# LeguinoNano.net
KiCad netlist of a schematic drawn in EAGLE
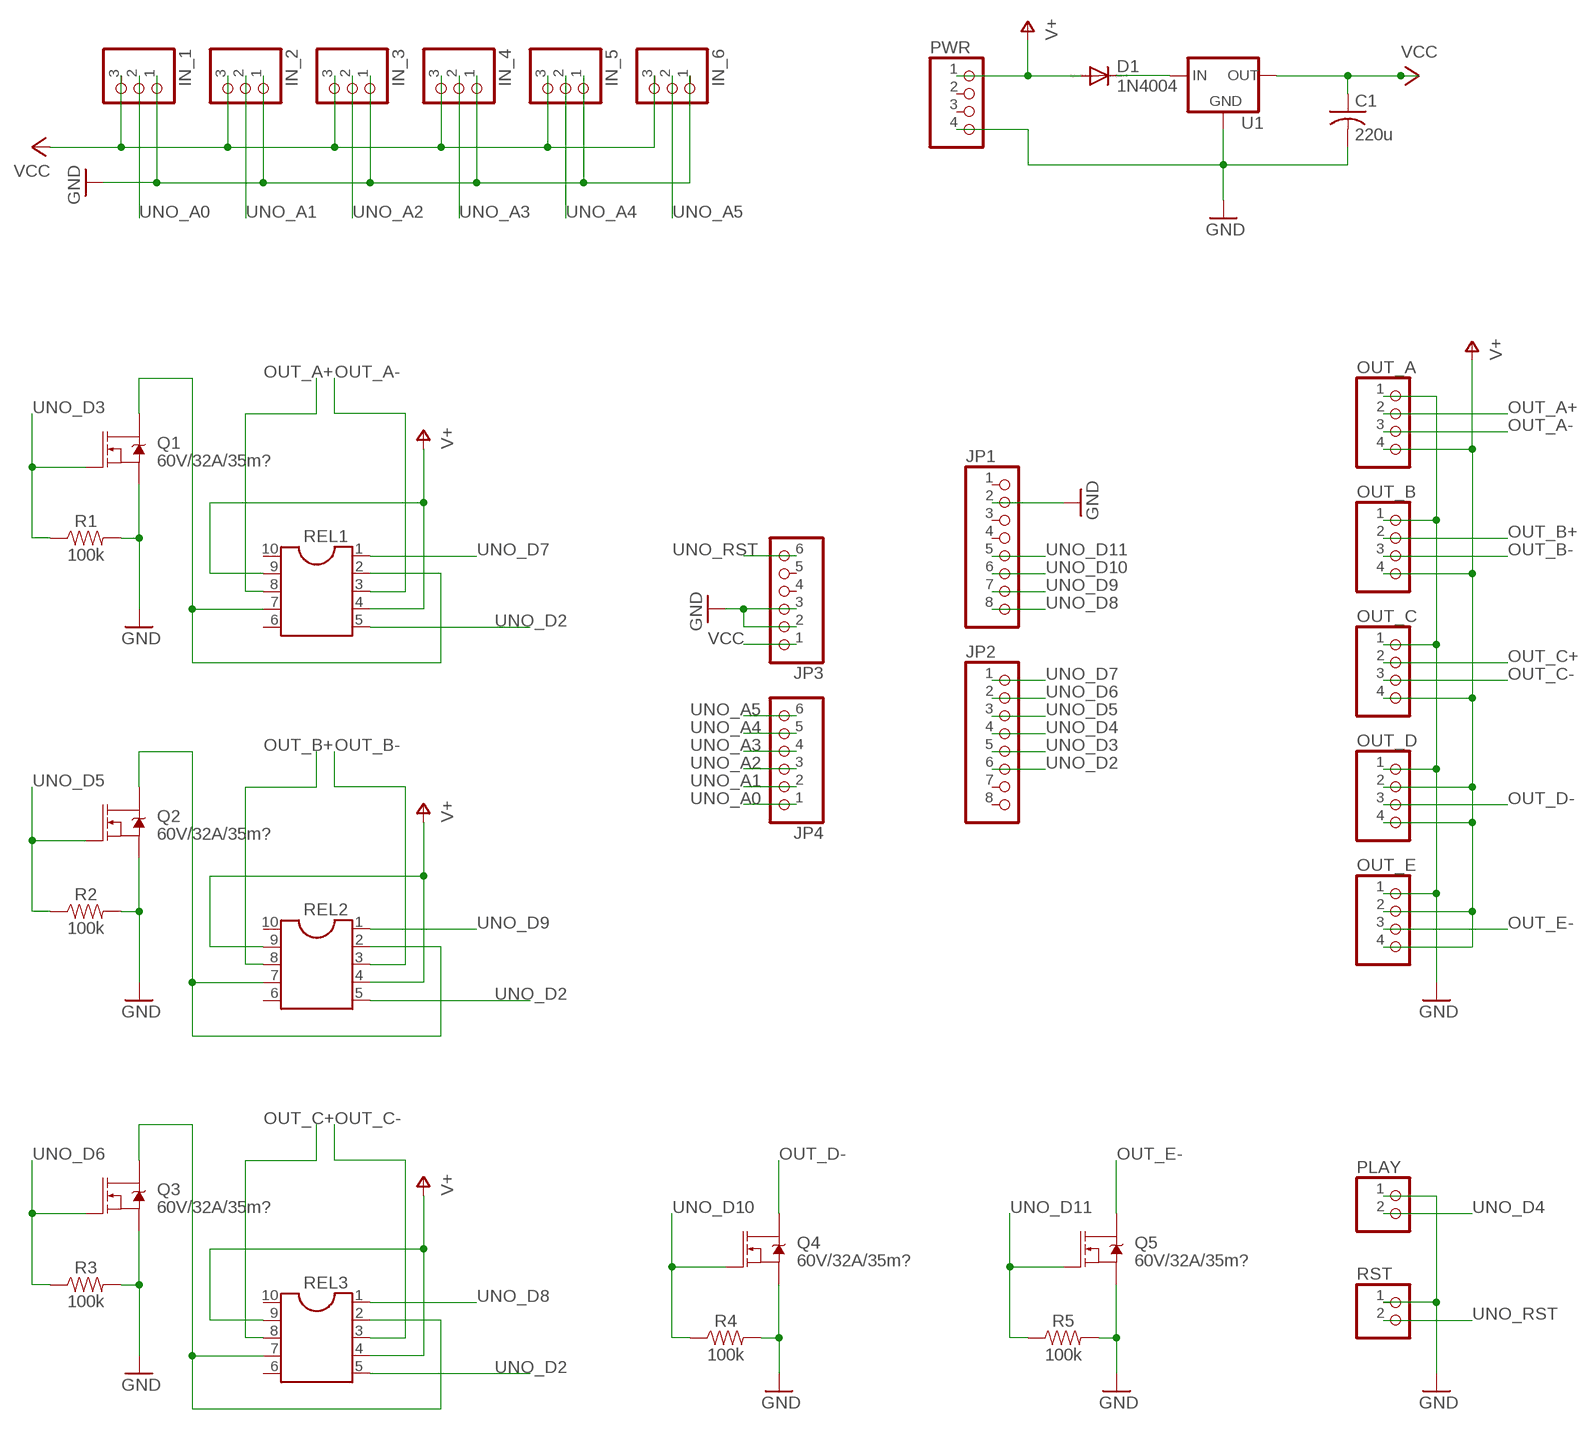
[diagram p0: schematic, sheet 1]

(export (version "E")
  (design (tool "Eeschema 10.0.6"))
  (components
    (comp (ref "C1")
      (value "220u")
      (footprint "eagle-import:C050-030X075")
      (libsource (lib "eagle-import") (part "C-US050-030X075"))
    )
    (comp (ref "D1")
      (value "1N4004")
      (footprint "eagle-import:DO41-10")
      (libsource (lib "eagle-import") (part "1N4004"))
    )
    (comp (ref "IN_1")
      (value "PINHD-1X3")
      (footprint "eagle-import:1X03")
      (libsource (lib "eagle-import") (part "PINHD-1X3"))
    )
    (comp (ref "IN_2")
      (value "PINHD-1X3")
      (footprint "eagle-import:1X03")
      (libsource (lib "eagle-import") (part "PINHD-1X3"))
    )
    (comp (ref "IN_3")
      (value "PINHD-1X3")
      (footprint "eagle-import:1X03")
      (libsource (lib "eagle-import") (part "PINHD-1X3"))
    )
    (comp (ref "IN_4")
      (value "PINHD-1X3")
      (footprint "eagle-import:1X03")
      (libsource (lib "eagle-import") (part "PINHD-1X3"))
    )
    (comp (ref "IN_5")
      (value "PINHD-1X3")
      (footprint "eagle-import:1X03")
      (libsource (lib "eagle-import") (part "PINHD-1X3"))
    )
    (comp (ref "IN_6")
      (value "PINHD-1X3")
      (footprint "eagle-import:1X03")
      (libsource (lib "eagle-import") (part "PINHD-1X3"))
    )
    (comp (ref "JP1")
      (value "PINHD-1X8")
      (footprint "eagle-import:1X08")
      (libsource (lib "eagle-import") (part "PINHD-1X8"))
    )
    (comp (ref "JP2")
      (value "PINHD-1X8")
      (footprint "eagle-import:1X08")
      (libsource (lib "eagle-import") (part "PINHD-1X8"))
    )
    (comp (ref "JP3")
      (value "PINHD-1X6")
      (footprint "eagle-import:1X06")
      (libsource (lib "eagle-import") (part "PINHD-1X6"))
    )
    (comp (ref "JP4")
      (value "PINHD-1X6")
      (footprint "eagle-import:1X06")
      (libsource (lib "eagle-import") (part "PINHD-1X6"))
    )
    (comp (ref "OUT_A")
      (value "PINHD-1X4")
      (footprint "eagle-import:1X04")
      (libsource (lib "eagle-import") (part "PINHD-1X4"))
    )
    (comp (ref "OUT_B")
      (value "PINHD-1X4")
      (footprint "eagle-import:1X04")
      (libsource (lib "eagle-import") (part "PINHD-1X4"))
    )
    (comp (ref "OUT_C")
      (value "PINHD-1X4")
      (footprint "eagle-import:1X04")
      (libsource (lib "eagle-import") (part "PINHD-1X4"))
    )
    (comp (ref "OUT_D")
      (value "PINHD-1X4")
      (footprint "eagle-import:1X04")
      (libsource (lib "eagle-import") (part "PINHD-1X4"))
    )
    (comp (ref "OUT_E")
      (value "PINHD-1X4")
      (footprint "eagle-import:1X04")
      (libsource (lib "eagle-import") (part "PINHD-1X4"))
    )
    (comp (ref "PLAY")
      (value "PINHD-1X2")
      (footprint "eagle-import:1X02")
      (libsource (lib "eagle-import") (part "PINHD-1X2"))
    )
    (comp (ref "PWR")
      (value "PINHD-1X4")
      (footprint "eagle-import:1X04")
      (libsource (lib "eagle-import") (part "PINHD-1X4"))
    )
    (comp (ref "Q1")
      (value "60V/32A/35m?")
      (footprint "eagle-import:TO220V")
      (libsource (lib "eagle-import") (part "MOSFET-NCH-FQP30N06L"))
    )
    (comp (ref "Q2")
      (value "60V/32A/35m?")
      (footprint "eagle-import:TO220V")
      (libsource (lib "eagle-import") (part "MOSFET-NCH-FQP30N06L"))
    )
    (comp (ref "Q3")
      (value "60V/32A/35m?")
      (footprint "eagle-import:TO220V")
      (libsource (lib "eagle-import") (part "MOSFET-NCH-FQP30N06L"))
    )
    (comp (ref "Q4")
      (value "60V/32A/35m?")
      (footprint "eagle-import:TO220V")
      (libsource (lib "eagle-import") (part "MOSFET-NCH-FQP30N06L"))
    )
    (comp (ref "Q5")
      (value "60V/32A/35m?")
      (footprint "eagle-import:TO220V")
      (libsource (lib "eagle-import") (part "MOSFET-NCH-FQP30N06L"))
    )
    (comp (ref "R1")
      (value "100k")
      (footprint "eagle-import:AXIAL-0.3")
      (libsource (lib "eagle-import") (part "100KOHM-HORIZ-1/4W-1%"))
    )
    (comp (ref "R2")
      (value "100k")
      (footprint "eagle-import:AXIAL-0.3")
      (libsource (lib "eagle-import") (part "100KOHM-HORIZ-1/4W-1%"))
    )
    (comp (ref "R3")
      (value "100k")
      (footprint "eagle-import:AXIAL-0.3")
      (libsource (lib "eagle-import") (part "100KOHM-HORIZ-1/4W-1%"))
    )
    (comp (ref "R4")
      (value "100k")
      (footprint "eagle-import:AXIAL-0.3")
      (libsource (lib "eagle-import") (part "100KOHM-HORIZ-1/4W-1%"))
    )
    (comp (ref "R5")
      (value "100k")
      (footprint "eagle-import:AXIAL-0.3")
      (libsource (lib "eagle-import") (part "100KOHM-HORIZ-1/4W-1%"))
    )
    (comp (ref "REL1")
      (value "DIL10")
      (footprint "eagle-import:DIL10")
      (libsource (lib "eagle-import") (part "DIL10"))
    )
    (comp (ref "REL2")
      (value "DIL10")
      (footprint "eagle-import:DIL10")
      (libsource (lib "eagle-import") (part "DIL10"))
    )
    (comp (ref "REL3")
      (value "DIL10")
      (footprint "eagle-import:DIL10")
      (libsource (lib "eagle-import") (part "DIL10"))
    )
    (comp (ref "RST")
      (value "PINHD-1X2")
      (footprint "eagle-import:1X02")
      (libsource (lib "eagle-import") (part "PINHD-1X2"))
    )
    (comp (ref "U1")
      (value "V_REG_78XX-TO-220")
      (footprint "eagle-import:TO-220-ALT")
      (libsource (lib "eagle-import") (part "V_REG_78XX-TO-220"))
    )
  )
  (nets
    (net (code "1") (name "/OUT_A+") (class "Default")
      (node (ref "OUT_A") (pin "2") (pinfunction "2_2") (pintype "passive"))
      (node (ref "REL1") (pin "8") (pinfunction "8_8") (pintype "passive"))
    )
    (net (code "2") (name "/OUT_A-") (class "Default")
      (node (ref "OUT_A") (pin "3") (pinfunction "3_3") (pintype "passive"))
      (node (ref "REL1") (pin "3") (pinfunction "3_3") (pintype "passive"))
    )
    (net (code "3") (name "/OUT_B+") (class "Default")
      (node (ref "OUT_B") (pin "2") (pinfunction "2_2") (pintype "passive"))
      (node (ref "REL2") (pin "8") (pinfunction "8_8") (pintype "passive"))
    )
    (net (code "4") (name "/OUT_B-") (class "Default")
      (node (ref "OUT_B") (pin "3") (pinfunction "3_3") (pintype "passive"))
      (node (ref "REL2") (pin "3") (pinfunction "3_3") (pintype "passive"))
    )
    (net (code "5") (name "/OUT_C+") (class "Default")
      (node (ref "OUT_C") (pin "2") (pinfunction "2_2") (pintype "passive"))
      (node (ref "REL3") (pin "8") (pinfunction "8_8") (pintype "passive"))
    )
    (net (code "6") (name "/OUT_C-") (class "Default")
      (node (ref "OUT_C") (pin "3") (pinfunction "3_3") (pintype "passive"))
      (node (ref "REL3") (pin "3") (pinfunction "3_3") (pintype "passive"))
    )
    (net (code "7") (name "/OUT_D-") (class "Default")
      (node (ref "OUT_D") (pin "3") (pinfunction "3_3") (pintype "passive"))
      (node (ref "Q4") (pin "2") (pinfunction "D_2") (pintype "bidirectional"))
    )
    (net (code "8") (name "/OUT_E-") (class "Default")
      (node (ref "OUT_E") (pin "3") (pinfunction "3_3") (pintype "passive"))
      (node (ref "Q5") (pin "2") (pinfunction "D_2") (pintype "bidirectional"))
    )
    (net (code "9") (name "/UNO_A0") (class "Default")
      (node (ref "IN_1") (pin "2") (pinfunction "2_2") (pintype "passive"))
      (node (ref "JP4") (pin "1") (pinfunction "1_1") (pintype "passive"))
    )
    (net (code "10") (name "/UNO_A1") (class "Default")
      (node (ref "IN_2") (pin "2") (pinfunction "2_2") (pintype "passive"))
      (node (ref "JP4") (pin "2") (pinfunction "2_2") (pintype "passive"))
    )
    (net (code "11") (name "/UNO_A2") (class "Default")
      (node (ref "IN_3") (pin "2") (pinfunction "2_2") (pintype "passive"))
      (node (ref "JP4") (pin "3") (pinfunction "3_3") (pintype "passive"))
    )
    (net (code "12") (name "/UNO_A3") (class "Default")
      (node (ref "IN_4") (pin "2") (pinfunction "2_2") (pintype "passive"))
      (node (ref "JP4") (pin "4") (pinfunction "4_4") (pintype "passive"))
    )
    (net (code "13") (name "/UNO_A4") (class "Default")
      (node (ref "IN_5") (pin "2") (pinfunction "2_2") (pintype "passive"))
      (node (ref "JP4") (pin "5") (pinfunction "5_5") (pintype "passive"))
    )
    (net (code "14") (name "/UNO_A5") (class "Default")
      (node (ref "IN_6") (pin "2") (pinfunction "2_2") (pintype "passive"))
      (node (ref "JP4") (pin "6") (pinfunction "6_6") (pintype "passive"))
    )
    (net (code "15") (name "/UNO_D2") (class "Default")
      (node (ref "JP2") (pin "6") (pinfunction "6_6") (pintype "passive"))
      (node (ref "REL1") (pin "5") (pinfunction "5_5") (pintype "passive"))
      (node (ref "REL2") (pin "5") (pinfunction "5_5") (pintype "passive"))
      (node (ref "REL3") (pin "5") (pinfunction "5_5") (pintype "passive"))
    )
    (net (code "16") (name "/UNO_D3") (class "Default")
      (node (ref "JP2") (pin "5") (pinfunction "5_5") (pintype "passive"))
      (node (ref "Q1") (pin "1") (pinfunction "G_1") (pintype "bidirectional"))
      (node (ref "R1") (pin "P$1") (pinfunction "1_P$1") (pintype "passive"))
    )
    (net (code "17") (name "/UNO_D4") (class "Default")
      (node (ref "JP2") (pin "4") (pinfunction "4_4") (pintype "passive"))
      (node (ref "PLAY") (pin "2") (pinfunction "2_2") (pintype "passive"))
    )
    (net (code "18") (name "/UNO_D5") (class "Default")
      (node (ref "JP2") (pin "3") (pinfunction "3_3") (pintype "passive"))
      (node (ref "Q2") (pin "1") (pinfunction "G_1") (pintype "bidirectional"))
      (node (ref "R2") (pin "P$1") (pinfunction "1_P$1") (pintype "passive"))
    )
    (net (code "19") (name "/UNO_D6") (class "Default")
      (node (ref "JP2") (pin "2") (pinfunction "2_2") (pintype "passive"))
      (node (ref "Q3") (pin "1") (pinfunction "G_1") (pintype "bidirectional"))
      (node (ref "R3") (pin "P$1") (pinfunction "1_P$1") (pintype "passive"))
    )
    (net (code "20") (name "/UNO_D7") (class "Default")
      (node (ref "JP2") (pin "1") (pinfunction "1_1") (pintype "passive"))
      (node (ref "REL1") (pin "1") (pinfunction "1_1") (pintype "passive"))
    )
    (net (code "21") (name "/UNO_D8") (class "Default")
      (node (ref "JP1") (pin "8") (pinfunction "8_8") (pintype "passive"))
      (node (ref "REL3") (pin "1") (pinfunction "1_1") (pintype "passive"))
    )
    (net (code "22") (name "/UNO_D9") (class "Default")
      (node (ref "JP1") (pin "7") (pinfunction "7_7") (pintype "passive"))
      (node (ref "REL2") (pin "1") (pinfunction "1_1") (pintype "passive"))
    )
    (net (code "23") (name "/UNO_D10") (class "Default")
      (node (ref "JP1") (pin "6") (pinfunction "6_6") (pintype "passive"))
      (node (ref "Q4") (pin "1") (pinfunction "G_1") (pintype "bidirectional"))
      (node (ref "R4") (pin "P$1") (pinfunction "1_P$1") (pintype "passive"))
    )
    (net (code "24") (name "/UNO_D11") (class "Default")
      (node (ref "JP1") (pin "5") (pinfunction "5_5") (pintype "passive"))
      (node (ref "Q5") (pin "1") (pinfunction "G_1") (pintype "bidirectional"))
      (node (ref "R5") (pin "P$1") (pinfunction "1_P$1") (pintype "passive"))
    )
    (net (code "25") (name "/UNO_RST") (class "Default")
      (node (ref "JP3") (pin "6") (pinfunction "6_6") (pintype "passive"))
      (node (ref "RST") (pin "2") (pinfunction "2_2") (pintype "passive"))
    )
    (net (code "26") (name "GND") (class "Default")
      (node (ref "C1") (pin "2") (pinfunction "2_2") (pintype "passive"))
      (node (ref "IN_1") (pin "1") (pinfunction "1_1") (pintype "passive"))
      (node (ref "IN_2") (pin "1") (pinfunction "1_1") (pintype "passive"))
      (node (ref "IN_3") (pin "1") (pinfunction "1_1") (pintype "passive"))
      (node (ref "IN_4") (pin "1") (pinfunction "1_1") (pintype "passive"))
      (node (ref "IN_5") (pin "1") (pinfunction "1_1") (pintype "passive"))
      (node (ref "IN_6") (pin "1") (pinfunction "1_1") (pintype "passive"))
      (node (ref "JP1") (pin "2") (pinfunction "2_2") (pintype "passive"))
      (node (ref "JP3") (pin "2") (pinfunction "2_2") (pintype "passive"))
      (node (ref "JP3") (pin "3") (pinfunction "3_3") (pintype "passive"))
      (node (ref "OUT_A") (pin "1") (pinfunction "1_1") (pintype "passive"))
      (node (ref "OUT_B") (pin "1") (pinfunction "1_1") (pintype "passive"))
      (node (ref "OUT_C") (pin "1") (pinfunction "1_1") (pintype "passive"))
      (node (ref "OUT_D") (pin "1") (pinfunction "1_1") (pintype "passive"))
      (node (ref "OUT_E") (pin "1") (pinfunction "1_1") (pintype "passive"))
      (node (ref "PLAY") (pin "1") (pinfunction "1_1") (pintype "passive"))
      (node (ref "PWR") (pin "4") (pinfunction "4_4") (pintype "passive"))
      (node (ref "Q1") (pin "3") (pinfunction "S_3") (pintype "bidirectional"))
      (node (ref "Q2") (pin "3") (pinfunction "S_3") (pintype "bidirectional"))
      (node (ref "Q3") (pin "3") (pinfunction "S_3") (pintype "bidirectional"))
      (node (ref "Q4") (pin "3") (pinfunction "S_3") (pintype "bidirectional"))
      (node (ref "Q5") (pin "3") (pinfunction "S_3") (pintype "bidirectional"))
      (node (ref "R1") (pin "P$2") (pinfunction "2_P$2") (pintype "passive"))
      (node (ref "R2") (pin "P$2") (pinfunction "2_P$2") (pintype "passive"))
      (node (ref "R3") (pin "P$2") (pinfunction "2_P$2") (pintype "passive"))
      (node (ref "R4") (pin "P$2") (pinfunction "2_P$2") (pintype "passive"))
      (node (ref "R5") (pin "P$2") (pinfunction "2_P$2") (pintype "passive"))
      (node (ref "RST") (pin "1") (pinfunction "1_1") (pintype "passive"))
      (node (ref "U1") (pin "GND") (pinfunction "GND_GND") (pintype "input"))
    )
    (net (code "27") (name "Net-(D1-PadC)") (class "Default")
      (node (ref "D1") (pin "C") (pinfunction "C_C") (pintype "passive"))
      (node (ref "U1") (pin "IN") (pinfunction "IN_IN") (pintype "input"))
    )
    (net (code "28") (name "Net-(Q1-D)") (class "Default")
      (node (ref "Q1") (pin "2") (pinfunction "D_2") (pintype "bidirectional"))
      (node (ref "REL1") (pin "2") (pinfunction "2_2") (pintype "passive"))
      (node (ref "REL1") (pin "7") (pinfunction "7_7") (pintype "passive"))
    )
    (net (code "29") (name "Net-(Q2-D)") (class "Default")
      (node (ref "Q2") (pin "2") (pinfunction "D_2") (pintype "bidirectional"))
      (node (ref "REL2") (pin "2") (pinfunction "2_2") (pintype "passive"))
      (node (ref "REL2") (pin "7") (pinfunction "7_7") (pintype "passive"))
    )
    (net (code "30") (name "Net-(Q3-D)") (class "Default")
      (node (ref "Q3") (pin "2") (pinfunction "D_2") (pintype "bidirectional"))
      (node (ref "REL3") (pin "2") (pinfunction "2_2") (pintype "passive"))
      (node (ref "REL3") (pin "7") (pinfunction "7_7") (pintype "passive"))
    )
    (net (code "31") (name "V+") (class "Default")
      (node (ref "D1") (pin "A") (pinfunction "A_A") (pintype "passive"))
      (node (ref "OUT_A") (pin "4") (pinfunction "4_4") (pintype "passive"))
      (node (ref "OUT_B") (pin "4") (pinfunction "4_4") (pintype "passive"))
      (node (ref "OUT_C") (pin "4") (pinfunction "4_4") (pintype "passive"))
      (node (ref "OUT_D") (pin "2") (pinfunction "2_2") (pintype "passive"))
      (node (ref "OUT_D") (pin "4") (pinfunction "4_4") (pintype "passive"))
      (node (ref "OUT_E") (pin "2") (pinfunction "2_2") (pintype "passive"))
      (node (ref "OUT_E") (pin "4") (pinfunction "4_4") (pintype "passive"))
      (node (ref "PWR") (pin "1") (pinfunction "1_1") (pintype "passive"))
      (node (ref "REL1") (pin "4") (pinfunction "4_4") (pintype "passive"))
      (node (ref "REL1") (pin "9") (pinfunction "9_9") (pintype "passive"))
      (node (ref "REL2") (pin "4") (pinfunction "4_4") (pintype "passive"))
      (node (ref "REL2") (pin "9") (pinfunction "9_9") (pintype "passive"))
      (node (ref "REL3") (pin "4") (pinfunction "4_4") (pintype "passive"))
      (node (ref "REL3") (pin "9") (pinfunction "9_9") (pintype "passive"))
    )
    (net (code "32") (name "VCC") (class "Default")
      (node (ref "C1") (pin "1") (pinfunction "1_1") (pintype "passive"))
      (node (ref "IN_1") (pin "3") (pinfunction "3_3") (pintype "passive"))
      (node (ref "IN_2") (pin "3") (pinfunction "3_3") (pintype "passive"))
      (node (ref "IN_3") (pin "3") (pinfunction "3_3") (pintype "passive"))
      (node (ref "IN_4") (pin "3") (pinfunction "3_3") (pintype "passive"))
      (node (ref "IN_5") (pin "3") (pinfunction "3_3") (pintype "passive"))
      (node (ref "IN_6") (pin "3") (pinfunction "3_3") (pintype "passive"))
      (node (ref "JP3") (pin "1") (pinfunction "1_1") (pintype "passive"))
      (node (ref "U1") (pin "OUT") (pinfunction "OUT_OUT") (pintype "passive"))
    )
    (net (code "33") (name "unconnected-(JP1-Pad1)") (class "Default")
      (node (ref "JP1") (pin "1") (pinfunction "1_1") (pintype "passive"))
    )
    (net (code "34") (name "unconnected-(JP1-Pad3)") (class "Default")
      (node (ref "JP1") (pin "3") (pinfunction "3_3") (pintype "passive"))
    )
    (net (code "35") (name "unconnected-(JP1-Pad4)") (class "Default")
      (node (ref "JP1") (pin "4") (pinfunction "4_4") (pintype "passive"))
    )
    (net (code "36") (name "unconnected-(JP2-Pad7)") (class "Default")
      (node (ref "JP2") (pin "7") (pinfunction "7_7") (pintype "passive"))
    )
    (net (code "37") (name "unconnected-(JP2-Pad8)") (class "Default")
      (node (ref "JP2") (pin "8") (pinfunction "8_8") (pintype "passive"))
    )
    (net (code "38") (name "unconnected-(JP3-Pad4)") (class "Default")
      (node (ref "JP3") (pin "4") (pinfunction "4_4") (pintype "passive"))
    )
    (net (code "39") (name "unconnected-(JP3-Pad5)") (class "Default")
      (node (ref "JP3") (pin "5") (pinfunction "5_5") (pintype "passive"))
    )
    (net (code "40") (name "unconnected-(PWR-Pad2)") (class "Default")
      (node (ref "PWR") (pin "2") (pinfunction "2_2") (pintype "passive"))
    )
    (net (code "41") (name "unconnected-(PWR-Pad3)") (class "Default")
      (node (ref "PWR") (pin "3") (pinfunction "3_3") (pintype "passive"))
    )
    (net (code "42") (name "unconnected-(REL1-Pad6)") (class "Default")
      (node (ref "REL1") (pin "6") (pinfunction "6_6") (pintype "passive"))
    )
    (net (code "43") (name "unconnected-(REL1-Pad10)") (class "Default")
      (node (ref "REL1") (pin "10") (pinfunction "10_10") (pintype "passive"))
    )
    (net (code "44") (name "unconnected-(REL2-Pad6)") (class "Default")
      (node (ref "REL2") (pin "6") (pinfunction "6_6") (pintype "passive"))
    )
    (net (code "45") (name "unconnected-(REL2-Pad10)") (class "Default")
      (node (ref "REL2") (pin "10") (pinfunction "10_10") (pintype "passive"))
    )
    (net (code "46") (name "unconnected-(REL3-Pad6)") (class "Default")
      (node (ref "REL3") (pin "6") (pinfunction "6_6") (pintype "passive"))
    )
    (net (code "47") (name "unconnected-(REL3-Pad10)") (class "Default")
      (node (ref "REL3") (pin "10") (pinfunction "10_10") (pintype "passive"))
    )
  )
)
